# PowerLatch.net
KiCad netlist of a schematic drawn in Altium Designer
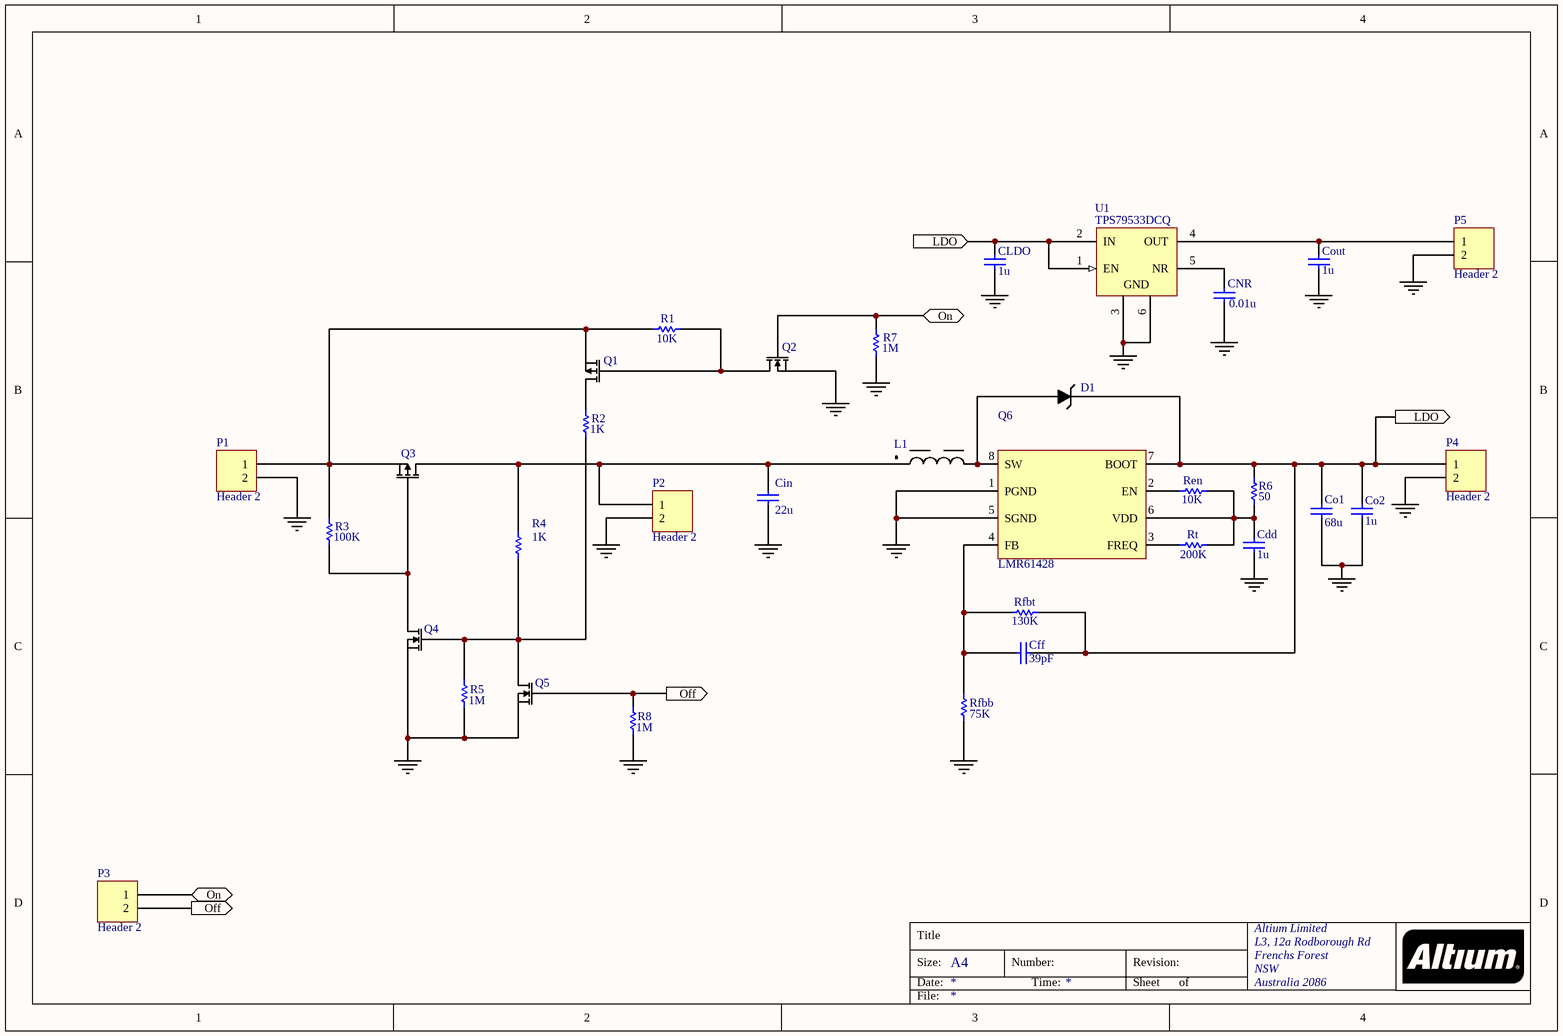
[diagram p0: PowerLatch.SchDoc]

(export (version "E")
  (design (tool "Eeschema 10.0.6"))
  (components
    (comp (ref "Cdd")
      (value "1u")
      (footprint "RESC1608X06N")
      (description "Capacitor")
      (fields (field (name "Comment") "Cap") (field (name "PUBLISHER") "Altium Limited"))
      (libsource (lib "Miscellaneous Devices") (part "Cap"))
    )
    (comp (ref "Cff")
      (value "39pF")
      (footprint "RESC1608X06N")
      (description "Capacitor")
      (fields (field (name "Comment") "Cap") (field (name "PUBLISHER") "Altium Limited"))
      (libsource (lib "Miscellaneous Devices") (part "Cap"))
    )
    (comp (ref "Cin")
      (value "22u")
      (footprint "CAPMP7343X31N")
      (description "Capacitor")
      (fields (field (name "Comment") "Cap") (field (name "PUBLISHER") "Altium Limited"))
      (libsource (lib "Miscellaneous Devices") (part "Cap"))
    )
    (comp (ref "CLDO")
      (value "1u")
      (footprint "RESC1608X06N")
      (description "Capacitor")
      (fields (field (name "Comment") "Cap") (field (name "PUBLISHER") "Altium Limited"))
      (libsource (lib "Miscellaneous Devices") (part "Cap"))
    )
    (comp (ref "CNR")
      (value "0.01u")
      (footprint "RESC1608X06N")
      (description "Capacitor")
      (fields (field (name "Comment") "Cap") (field (name "PUBLISHER") "Altium Limited"))
      (libsource (lib "Miscellaneous Devices") (part "Cap"))
    )
    (comp (ref "Co1")
      (value "68u")
      (footprint "CAP2812")
      (description "Capacitor")
      (fields (field (name "Comment") "Cap") (field (name "PUBLISHER") "Altium Limited"))
      (libsource (lib "Miscellaneous Devices") (part "Cap"))
    )
    (comp (ref "Co2")
      (value "1u")
      (footprint "CAPC0805")
      (description "Capacitor")
      (fields (field (name "Comment") "Cap") (field (name "PUBLISHER") "Altium Limited"))
      (libsource (lib "Miscellaneous Devices") (part "Cap"))
    )
    (comp (ref "Cout")
      (value "1u")
      (footprint "RESC1608X06N")
      (description "Capacitor")
      (fields (field (name "Comment") "Cap") (field (name "PUBLISHER") "Altium Limited"))
      (libsource (lib "Miscellaneous Devices") (part "Cap"))
    )
    (comp (ref "D1")
      (value "Schottky")
      (footprint "DIOM4326X23N")
      (libsource (lib "Schlib1") (part "Schottky"))
    )
    (comp (ref "L1")
      (value "Inductor")
      (footprint "INDP100100X51N")
      (libsource (lib "Schlib1") (part "Inductor"))
    )
    (comp (ref "P1")
      (value "Header 2")
      (footprint "PCBComponent_1")
      (description "Header, 2-Pin")
      (fields (field (name "PUBLISHER") "Altium Limited"))
      (libsource (lib "Miscellaneous Connectors") (part "Header 2"))
    )
    (comp (ref "P2")
      (value "Header 2")
      (footprint "PCBComponent_1")
      (description "Header, 2-Pin")
      (fields (field (name "PUBLISHER") "Altium Limited"))
      (libsource (lib "") (part "Header 2_1"))
    )
    (comp (ref "P3")
      (value "Header 2")
      (footprint "PCBComponent_1")
      (description "Header, 2-Pin")
      (fields (field (name "PUBLISHER") "Altium Limited"))
      (libsource (lib "Miscellaneous Connectors") (part "Header 2"))
    )
    (comp (ref "P4")
      (value "Header 2")
      (footprint "PCBComponent_1")
      (description "Header, 2-Pin")
      (fields (field (name "PUBLISHER") "Altium Limited"))
      (libsource (lib "") (part "Header 2_1"))
    )
    (comp (ref "P5")
      (value "Header 2")
      (footprint "PCBComponent_1")
      (description "Header, 2-Pin")
      (fields (field (name "PUBLISHER") "Altium Limited"))
      (libsource (lib "") (part "Header 2_1"))
    )
    (comp (ref "Q1")
      (value "MOSFET P-Channel")
      (footprint "SOT95P245X110-3N")
      (libsource (lib "Schlib1") (part "MOSFET P-Channel"))
    )
    (comp (ref "Q2")
      (value "MOSFET N-Channel")
      (footprint "SOT95P245X110-3N")
      (libsource (lib "Schlib1") (part "MOSFET N-Channel"))
    )
    (comp (ref "Q3")
      (value "MOSFET P-Channel")
      (footprint "SOT95P245X110-3N")
      (libsource (lib "Schlib1") (part "MOSFET P-Channel"))
    )
    (comp (ref "Q4")
      (value "MOSFET N-Channel")
      (footprint "SOT95P245X110-3N")
      (libsource (lib "Schlib1") (part "MOSFET N-Channel"))
    )
    (comp (ref "Q5")
      (value "MOSFET N-Channel")
      (footprint "SOT95P245X110-3N")
      (libsource (lib "Schlib1") (part "MOSFET N-Channel"))
    )
    (comp (ref "Q6")
      (value "LMR61428")
      (footprint "TSOP65P490X110-8N")
      (description "Step-Up Voltage Regulator")
      (libsource (lib "Schlib1") (part "LMR61428"))
    )
    (comp (ref "R1")
      (value "10K")
      (footprint "RESC1608X06N")
      (description "Resistor")
      (fields (field (name "Comment") "Res1") (field (name "PUBLISHER") "Altium Limited"))
      (libsource (lib "Miscellaneous Devices") (part "Res1"))
    )
    (comp (ref "R2")
      (value "1K")
      (footprint "RESC1608X06N")
      (description "Resistor")
      (fields (field (name "Comment") "Res1") (field (name "PUBLISHER") "Altium Limited"))
      (libsource (lib "Miscellaneous Devices") (part "Res1"))
    )
    (comp (ref "R3")
      (value "100K")
      (footprint "RESC1608X06N")
      (description "Resistor")
      (fields (field (name "Comment") "Res1") (field (name "PUBLISHER") "Altium Limited"))
      (libsource (lib "Miscellaneous Devices") (part "Res1"))
    )
    (comp (ref "R4")
      (value "1K")
      (footprint "RESC1608X06N")
      (description "Resistor")
      (fields (field (name "Comment") "Res1") (field (name "PUBLISHER") "Altium Limited"))
      (libsource (lib "Miscellaneous Devices") (part "Res1"))
    )
    (comp (ref "R5")
      (value "1M")
      (footprint "RESC1608X06N")
      (description "Resistor")
      (fields (field (name "Comment") "Res1") (field (name "PUBLISHER") "Altium Limited"))
      (libsource (lib "Miscellaneous Devices") (part "Res1"))
    )
    (comp (ref "R6")
      (value "50")
      (footprint "RESC1608X06N")
      (description "Resistor")
      (fields (field (name "Comment") "Res1") (field (name "PUBLISHER") "Altium Limited"))
      (libsource (lib "Miscellaneous Devices") (part "Res1"))
    )
    (comp (ref "R7")
      (value "1M")
      (footprint "RESC1608X06N")
      (description "Resistor")
      (fields (field (name "Comment") "Res1") (field (name "PUBLISHER") "Altium Limited"))
      (libsource (lib "Miscellaneous Devices") (part "Res1"))
    )
    (comp (ref "R8")
      (value "1M")
      (footprint "RESC1608X06N")
      (description "Resistor")
      (fields (field (name "Comment") "Res1") (field (name "PUBLISHER") "Altium Limited"))
      (libsource (lib "Miscellaneous Devices") (part "Res1"))
    )
    (comp (ref "Ren")
      (value "10K")
      (footprint "RESC1608X06N")
      (description "Resistor")
      (fields (field (name "Comment") "Res1") (field (name "PUBLISHER") "Altium Limited"))
      (libsource (lib "Miscellaneous Devices") (part "Res1"))
    )
    (comp (ref "Rfbb")
      (value "75K")
      (footprint "RESC1608X06N")
      (description "Resistor")
      (fields (field (name "Comment") "Res1") (field (name "PUBLISHER") "Altium Limited"))
      (libsource (lib "Miscellaneous Devices") (part "Res1"))
    )
    (comp (ref "Rfbt")
      (value "130K")
      (footprint "RESC1608X06N")
      (description "Resistor")
      (fields (field (name "Comment") "Res1") (field (name "PUBLISHER") "Altium Limited"))
      (libsource (lib "Miscellaneous Devices") (part "Res1"))
    )
    (comp (ref "Rt")
      (value "200K")
      (footprint "RESC1608X06N")
      (description "Resistor")
      (fields (field (name "Comment") "Res1") (field (name "PUBLISHER") "Altium Limited"))
      (libsource (lib "Miscellaneous Devices") (part "Res1"))
    )
    (comp (ref "U1")
      (value "TPS79533DCQ")
      (footprint "DCQ0006A_L")
      (fields (field (name "MANUFACTURER") "Texas Instruments"))
      (libsource (lib "Altium Content Vault") (part "TI-TPS7XXXXXXXX"))
    )
  )
  (nets
    (net (code "1") (name "/LDO") (class "Default")
      (node (ref "CLDO") (pin "2") (pinfunction "2_2") (pintype "passive"))
      (node (ref "Cff") (pin "1") (pinfunction "1_1") (pintype "passive"))
      (node (ref "Co1") (pin "1") (pinfunction "1_1") (pintype "passive"))
      (node (ref "Co2") (pin "2") (pinfunction "2_2") (pintype "passive"))
      (node (ref "D1") (pin "2") (pinfunction "K_2") (pintype "passive"))
      (node (ref "P4") (pin "1") (pinfunction "1_1") (pintype "passive"))
      (node (ref "Q6") (pin "7") (pinfunction "BOOT_7") (pintype "passive"))
      (node (ref "R6") (pin "1") (pinfunction "1_1") (pintype "passive"))
      (node (ref "Rfbt") (pin "2") (pinfunction "2_2") (pintype "passive"))
      (node (ref "U1") (pin "1") (pinfunction "EN_1") (pintype "input"))
      (node (ref "U1") (pin "2") (pinfunction "IN_2") (pintype "power_in"))
    )
    (net (code "2") (name "/Off") (class "Default")
      (node (ref "P3") (pin "2") (pinfunction "2_2") (pintype "passive"))
      (node (ref "Q5") (pin "1") (pinfunction "G_1") (pintype "passive"))
      (node (ref "R8") (pin "2") (pinfunction "2_2") (pintype "passive"))
    )
    (net (code "3") (name "/On") (class "Default")
      (node (ref "P3") (pin "1") (pinfunction "1_1") (pintype "passive"))
      (node (ref "Q2") (pin "1") (pinfunction "G_1") (pintype "passive"))
      (node (ref "R7") (pin "2") (pinfunction "2_2") (pintype "passive"))
    )
    (net (code "4") (name "GND") (class "Default")
      (node (ref "CLDO") (pin "1") (pinfunction "1_1") (pintype "passive"))
      (node (ref "CNR") (pin "1") (pinfunction "1_1") (pintype "passive"))
      (node (ref "Cdd") (pin "1") (pinfunction "1_1") (pintype "passive"))
      (node (ref "Cin") (pin "2") (pinfunction "2_2") (pintype "passive"))
      (node (ref "Co1") (pin "2") (pinfunction "2_2") (pintype "passive"))
      (node (ref "Co2") (pin "1") (pinfunction "1_1") (pintype "passive"))
      (node (ref "Cout") (pin "1") (pinfunction "1_1") (pintype "passive"))
      (node (ref "P1") (pin "2") (pinfunction "2_2") (pintype "passive"))
      (node (ref "P2") (pin "2") (pinfunction "2_2") (pintype "passive"))
      (node (ref "P4") (pin "2") (pinfunction "2_2") (pintype "passive"))
      (node (ref "P5") (pin "2") (pinfunction "2_2") (pintype "passive"))
      (node (ref "Q2") (pin "2") (pinfunction "S_2") (pintype "passive"))
      (node (ref "Q4") (pin "2") (pinfunction "S_2") (pintype "passive"))
      (node (ref "Q5") (pin "2") (pinfunction "S_2") (pintype "passive"))
      (node (ref "Q6") (pin "1") (pinfunction "PGND_1") (pintype "passive"))
      (node (ref "Q6") (pin "5") (pinfunction "SGND_5") (pintype "passive"))
      (node (ref "R5") (pin "1") (pinfunction "1_1") (pintype "passive"))
      (node (ref "R7") (pin "1") (pinfunction "1_1") (pintype "passive"))
      (node (ref "R8") (pin "1") (pinfunction "1_1") (pintype "passive"))
      (node (ref "Rfbb") (pin "2") (pinfunction "2_2") (pintype "passive"))
      (node (ref "U1") (pin "3") (pinfunction "GND_3") (pintype "power_in"))
      (node (ref "U1") (pin "6") (pinfunction "GND_6") (pintype "power_in"))
    )
    (net (code "5") (name "Net-(D1-A)") (class "Default")
      (node (ref "D1") (pin "1") (pinfunction "A_1") (pintype "passive"))
      (node (ref "L1") (pin "2") (pinfunction "2_2") (pintype "passive"))
      (node (ref "Q6") (pin "8") (pinfunction "SW_8") (pintype "passive"))
    )
    (net (code "6") (name "Net-(Q1-D)") (class "Default")
      (node (ref "Q1") (pin "3") (pinfunction "D_3") (pintype "passive"))
      (node (ref "R2") (pin "2") (pinfunction "2_2") (pintype "passive"))
    )
    (net (code "7") (name "Net-(Q1-G)") (class "Default")
      (node (ref "Q1") (pin "1") (pinfunction "G_1") (pintype "passive"))
      (node (ref "Q2") (pin "3") (pinfunction "D_3") (pintype "passive"))
      (node (ref "R1") (pin "1") (pinfunction "1_1") (pintype "passive"))
    )
    (net (code "8") (name "Net-(Q1-S)") (class "Default")
      (node (ref "P1") (pin "1") (pinfunction "1_1") (pintype "passive"))
      (node (ref "Q1") (pin "2") (pinfunction "S_2") (pintype "passive"))
      (node (ref "Q3") (pin "2") (pinfunction "S_2") (pintype "passive"))
      (node (ref "R1") (pin "2") (pinfunction "2_2") (pintype "passive"))
      (node (ref "R3") (pin "2") (pinfunction "2_2") (pintype "passive"))
    )
    (net (code "9") (name "Net-(Q3-D)") (class "Default")
      (node (ref "Cin") (pin "1") (pinfunction "1_1") (pintype "passive"))
      (node (ref "L1") (pin "1") (pinfunction "1_1") (pintype "passive"))
      (node (ref "P2") (pin "1") (pinfunction "1_1") (pintype "passive"))
      (node (ref "Q3") (pin "3") (pinfunction "D_3") (pintype "passive"))
      (node (ref "R4") (pin "2") (pinfunction "2_2") (pintype "passive"))
    )
    (net (code "10") (name "Net-(Q3-G)") (class "Default")
      (node (ref "Q3") (pin "1") (pinfunction "G_1") (pintype "passive"))
      (node (ref "Q4") (pin "3") (pinfunction "D_3") (pintype "passive"))
      (node (ref "R3") (pin "1") (pinfunction "1_1") (pintype "passive"))
    )
    (net (code "11") (name "Net-(Q4-G)") (class "Default")
      (node (ref "Q4") (pin "1") (pinfunction "G_1") (pintype "passive"))
      (node (ref "Q5") (pin "3") (pinfunction "D_3") (pintype "passive"))
      (node (ref "R2") (pin "1") (pinfunction "1_1") (pintype "passive"))
      (node (ref "R4") (pin "1") (pinfunction "1_1") (pintype "passive"))
      (node (ref "R5") (pin "2") (pinfunction "2_2") (pintype "passive"))
    )
    (net (code "12") (name "Net-(Q6-EN)") (class "Default")
      (node (ref "Q6") (pin "2") (pinfunction "EN_2") (pintype "passive"))
      (node (ref "Ren") (pin "1") (pinfunction "1_1") (pintype "passive"))
    )
    (net (code "13") (name "Net-(Q6-FB)") (class "Default")
      (node (ref "Cff") (pin "2") (pinfunction "2_2") (pintype "passive"))
      (node (ref "Q6") (pin "4") (pinfunction "FB_4") (pintype "passive"))
      (node (ref "Rfbb") (pin "1") (pinfunction "1_1") (pintype "passive"))
      (node (ref "Rfbt") (pin "1") (pinfunction "1_1") (pintype "passive"))
    )
    (net (code "14") (name "Net-(Q6-FREQ)") (class "Default")
      (node (ref "Q6") (pin "3") (pinfunction "FREQ_3") (pintype "passive"))
      (node (ref "Rt") (pin "1") (pinfunction "1_1") (pintype "passive"))
    )
    (net (code "15") (name "Net-(Q6-VDD)") (class "Default")
      (node (ref "Cdd") (pin "2") (pinfunction "2_2") (pintype "passive"))
      (node (ref "Q6") (pin "6") (pinfunction "VDD_6") (pintype "passive"))
      (node (ref "R6") (pin "2") (pinfunction "2_2") (pintype "passive"))
      (node (ref "Ren") (pin "2") (pinfunction "2_2") (pintype "passive"))
      (node (ref "Rt") (pin "2") (pinfunction "2_2") (pintype "passive"))
    )
    (net (code "16") (name "Net-(U1-NR)") (class "Default")
      (node (ref "CNR") (pin "2") (pinfunction "2_2") (pintype "passive"))
      (node (ref "U1") (pin "5") (pinfunction "NR_5") (pintype "passive"))
    )
    (net (code "17") (name "Net-(U1-OUT)") (class "Default")
      (node (ref "Cout") (pin "2") (pinfunction "2_2") (pintype "passive"))
      (node (ref "P5") (pin "1") (pinfunction "1_1") (pintype "passive"))
      (node (ref "U1") (pin "4") (pinfunction "OUT_4") (pintype "power_in"))
    )
  )
)
